# bdm80.net
KiCad netlist of a schematic drawn in EAGLE
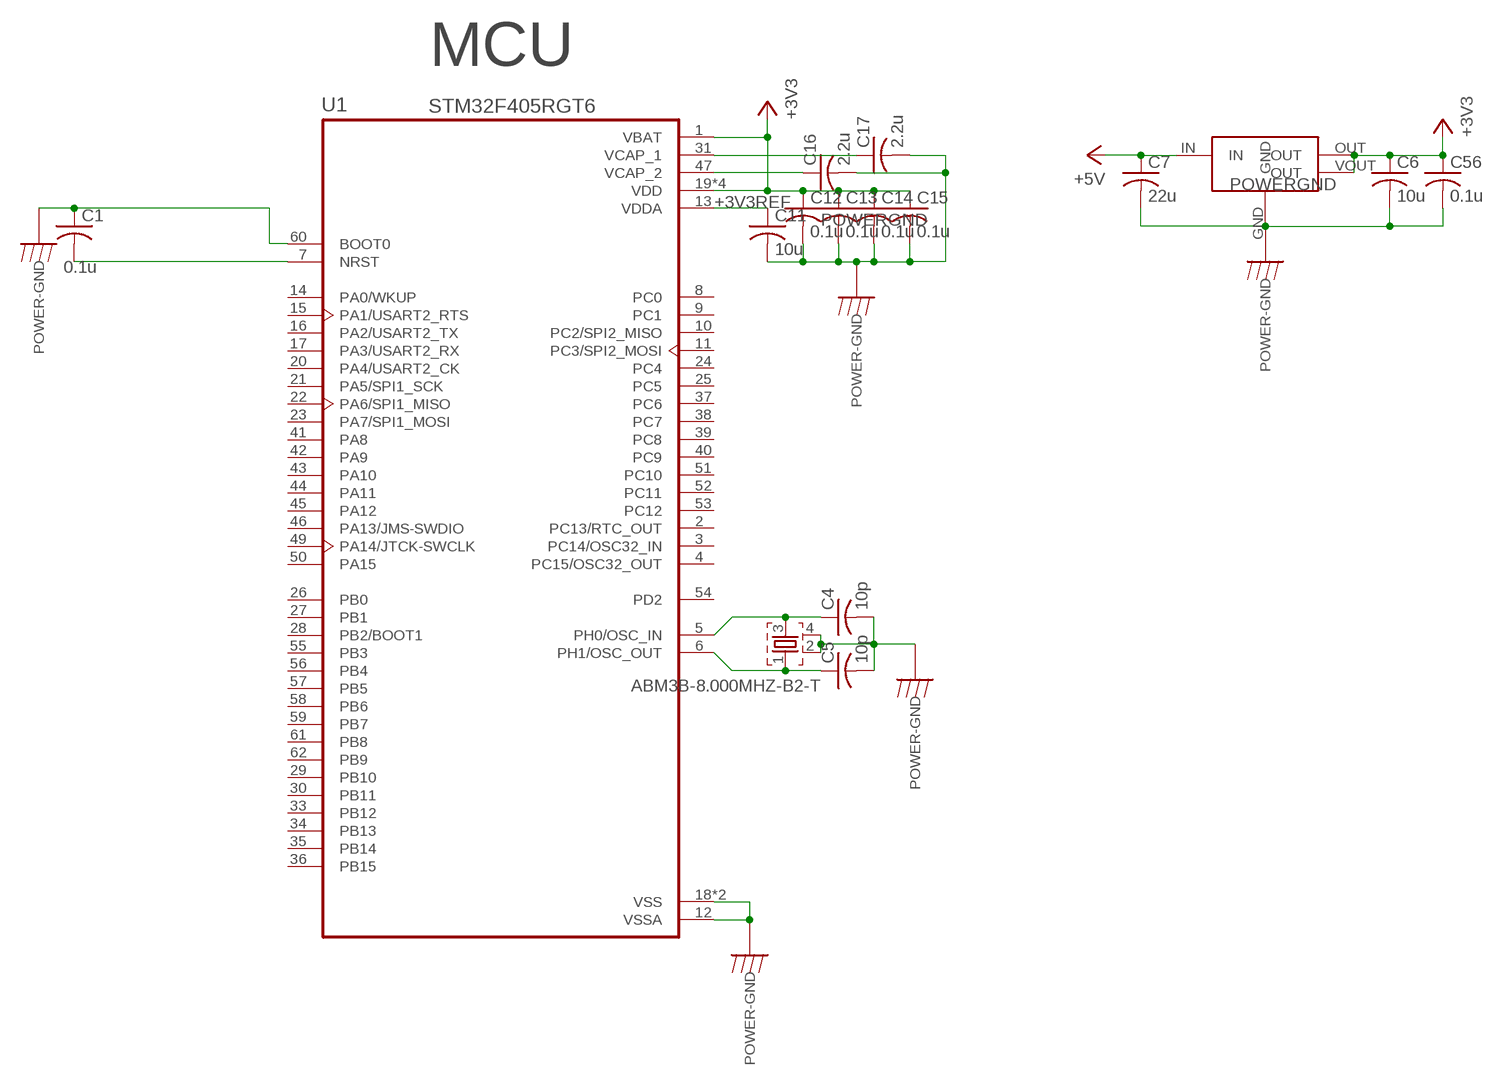
[diagram p0: schematic, sheet 1]

(export (version "E")
  (design (tool "Eeschema 10.0.6"))
  (components
    (comp (ref "C1")
      (value "0.1u")
      (footprint "eagle-import:2012-C")
      (libsource (lib "eagle-import") (part "C-2012"))
    )
    (comp (ref "C4")
      (value "10p")
      (footprint "eagle-import:1608")
      (libsource (lib "eagle-import") (part "C-1608"))
    )
    (comp (ref "C5")
      (value "10p")
      (footprint "eagle-import:1608")
      (libsource (lib "eagle-import") (part "C-1608"))
    )
    (comp (ref "C6")
      (value "10u")
      (footprint "eagle-import:2012-C")
      (libsource (lib "eagle-import") (part "C-2012"))
    )
    (comp (ref "C7")
      (value "22u")
      (footprint "eagle-import:2012-C")
      (libsource (lib "eagle-import") (part "C-2012"))
    )
    (comp (ref "C11")
      (value "10u")
      (footprint "eagle-import:2012-C")
      (libsource (lib "eagle-import") (part "C-2012"))
    )
    (comp (ref "C12")
      (value "0.1u")
      (footprint "eagle-import:2012-C")
      (libsource (lib "eagle-import") (part "C-2012"))
    )
    (comp (ref "C13")
      (value "0.1u")
      (footprint "eagle-import:2012-C")
      (libsource (lib "eagle-import") (part "C-2012"))
    )
    (comp (ref "C14")
      (value "0.1u")
      (footprint "eagle-import:2012-C")
      (libsource (lib "eagle-import") (part "C-2012"))
    )
    (comp (ref "C15")
      (value "0.1u")
      (footprint "eagle-import:2012-C")
      (libsource (lib "eagle-import") (part "C-2012"))
    )
    (comp (ref "C16")
      (value "2.2u")
      (footprint "eagle-import:2012-C")
      (libsource (lib "eagle-import") (part "C-2012"))
    )
    (comp (ref "C17")
      (value "2.2u")
      (footprint "eagle-import:2012-C")
      (libsource (lib "eagle-import") (part "C-2012"))
    )
    (comp (ref "C56")
      (value "0.1u")
      (footprint "eagle-import:2012-C")
      (libsource (lib "eagle-import") (part "C-2012"))
    )
    (comp (ref "IC1")
      (value "AZ1086H-3.3")
      (footprint "eagle-import:SOT223")
      (libsource (lib "eagle-import") (part "AZ1086?-H3.3"))
    )
    (comp (ref "U1")
      (value "STM32F405RGT6")
      (footprint "eagle-import:LQFP64")
      (fields (field (name "DIGI-KEY_PART_NUMBER") "497-11767-ND") (field (name "MF") "STMicroelectronics"))
      (libsource (lib "eagle-import") (part "STM32F405RGT6"))
    )
    (comp (ref "X1")
      (value "ABM3B-8.000MHZ-B2-T")
      (footprint "eagle-import:ABM3B-8.000MHZ-B2-T")
      (libsource (lib "eagle-import") (part "ABM3B-8.000MHZ-B2-T"))
    )
  )
  (nets
    (net (code "1") (name "+3V3") (class "Default")
      (node (ref "C12") (pin "1") (pinfunction "1_1") (pintype "passive"))
      (node (ref "C13") (pin "1") (pinfunction "1_1") (pintype "passive"))
      (node (ref "C14") (pin "1") (pinfunction "1_1") (pintype "passive"))
      (node (ref "C15") (pin "1") (pinfunction "1_1") (pintype "passive"))
      (node (ref "C56") (pin "1") (pinfunction "1_1") (pintype "passive"))
      (node (ref "C6") (pin "1") (pinfunction "1_1") (pintype "passive"))
      (node (ref "IC1") (pin "OUT") (pinfunction "OUT_OUT") (pintype "power_in"))
      (node (ref "IC1") (pin "VOUT") (pinfunction "OUT_VOUT") (pintype "power_in"))
      (node (ref "U1") (pin "1") (pinfunction "VBAT_1") (pintype "power_in"))
      (node (ref "U1") (pin "19") (pinfunction "VDD_19") (pintype "power_in"))
      (node (ref "U1") (pin "32") (pinfunction "VDD_32") (pintype "power_in"))
      (node (ref "U1") (pin "48") (pinfunction "VDD_48") (pintype "power_in"))
      (node (ref "U1") (pin "64") (pinfunction "VDD_64") (pintype "power_in"))
    )
    (net (code "2") (name "+5V") (class "Default")
      (node (ref "C7") (pin "1") (pinfunction "1_1") (pintype "passive"))
      (node (ref "IC1") (pin "IN") (pinfunction "IN_IN") (pintype "power_in"))
    )
    (net (code "3") (name "/+3V3REF") (class "Default")
      (node (ref "C11") (pin "1") (pinfunction "1_1") (pintype "passive"))
      (node (ref "U1") (pin "13") (pinfunction "VDDA_13") (pintype "power_in"))
    )
    (net (code "4") (name "Net-(U1-NRST)") (class "Default")
      (node (ref "C1") (pin "2") (pinfunction "2_2") (pintype "passive"))
      (node (ref "U1") (pin "7") (pinfunction "NRST_7") (pintype "bidirectional"))
    )
    (net (code "5") (name "Net-(U1-PH0{slash}OSC_IN)") (class "Default")
      (node (ref "C4") (pin "1") (pinfunction "1_1") (pintype "passive"))
      (node (ref "U1") (pin "5") (pinfunction "PH0/OSC_IN_5") (pintype "bidirectional"))
      (node (ref "X1") (pin "3") (pinfunction "3_3") (pintype "passive"))
    )
    (net (code "6") (name "Net-(U1-PH1{slash}OSC_OUT)") (class "Default")
      (node (ref "C5") (pin "1") (pinfunction "1_1") (pintype "passive"))
      (node (ref "U1") (pin "6") (pinfunction "PH1/OSC_OUT_6") (pintype "bidirectional"))
      (node (ref "X1") (pin "1") (pinfunction "1_1") (pintype "passive"))
    )
    (net (code "7") (name "Net-(U1-VCAP_1)") (class "Default")
      (node (ref "C17") (pin "1") (pinfunction "1_1") (pintype "passive"))
      (node (ref "U1") (pin "31") (pinfunction "VCAP_1_31") (pintype "power_in"))
    )
    (net (code "8") (name "Net-(U1-VCAP_2)") (class "Default")
      (node (ref "C16") (pin "1") (pinfunction "1_1") (pintype "passive"))
      (node (ref "U1") (pin "47") (pinfunction "VCAP_2_47") (pintype "power_in"))
    )
    (net (code "9") (name "POWERGND") (class "Default")
      (node (ref "C1") (pin "1") (pinfunction "1_1") (pintype "passive"))
      (node (ref "C11") (pin "2") (pinfunction "2_2") (pintype "passive"))
      (node (ref "C12") (pin "2") (pinfunction "2_2") (pintype "passive"))
      (node (ref "C13") (pin "2") (pinfunction "2_2") (pintype "passive"))
      (node (ref "C14") (pin "2") (pinfunction "2_2") (pintype "passive"))
      (node (ref "C15") (pin "2") (pinfunction "2_2") (pintype "passive"))
      (node (ref "C16") (pin "2") (pinfunction "2_2") (pintype "passive"))
      (node (ref "C17") (pin "2") (pinfunction "2_2") (pintype "passive"))
      (node (ref "C4") (pin "2") (pinfunction "2_2") (pintype "passive"))
      (node (ref "C5") (pin "2") (pinfunction "2_2") (pintype "passive"))
      (node (ref "C56") (pin "2") (pinfunction "2_2") (pintype "passive"))
      (node (ref "C6") (pin "2") (pinfunction "2_2") (pintype "passive"))
      (node (ref "C7") (pin "2") (pinfunction "2_2") (pintype "passive"))
      (node (ref "IC1") (pin "GND") (pinfunction "GND_GND") (pintype "power_in"))
      (node (ref "U1") (pin "12") (pinfunction "VSSA_12") (pintype "power_in"))
      (node (ref "U1") (pin "18") (pinfunction "VSS_18") (pintype "power_in"))
      (node (ref "U1") (pin "60") (pinfunction "BOOT0_60") (pintype "bidirectional"))
      (node (ref "U1") (pin "63") (pinfunction "VSS_63") (pintype "power_in"))
      (node (ref "X1") (pin "2") (pinfunction "2_2") (pintype "passive"))
      (node (ref "X1") (pin "4") (pinfunction "4_4") (pintype "passive"))
    )
    (net (code "10") (name "unconnected-(U1-PA0{slash}WKUP-Pad14)") (class "Default")
      (node (ref "U1") (pin "14") (pinfunction "PA0/WKUP_14") (pintype "bidirectional"))
    )
    (net (code "11") (name "unconnected-(U1-PA1{slash}USART2_RTS-Pad15)") (class "Default")
      (node (ref "U1") (pin "15") (pinfunction "PA1/USART2_RTS_15") (pintype "bidirectional"))
    )
    (net (code "12") (name "unconnected-(U1-PA2{slash}USART2_TX-Pad16)") (class "Default")
      (node (ref "U1") (pin "16") (pinfunction "PA2/USART2_TX_16") (pintype "bidirectional"))
    )
    (net (code "13") (name "unconnected-(U1-PA3{slash}USART2_RX-Pad17)") (class "Default")
      (node (ref "U1") (pin "17") (pinfunction "PA3/USART2_RX_17") (pintype "bidirectional"))
    )
    (net (code "14") (name "unconnected-(U1-PA4{slash}USART2_CK-Pad20)") (class "Default")
      (node (ref "U1") (pin "20") (pinfunction "PA4/USART2_CK_20") (pintype "bidirectional"))
    )
    (net (code "15") (name "unconnected-(U1-PA5{slash}SPI1_SCK-Pad21)") (class "Default")
      (node (ref "U1") (pin "21") (pinfunction "PA5/SPI1_SCK_21") (pintype "bidirectional"))
    )
    (net (code "16") (name "unconnected-(U1-PA6{slash}SPI1_MISO-Pad22)") (class "Default")
      (node (ref "U1") (pin "22") (pinfunction "PA6/SPI1_MISO_22") (pintype "bidirectional"))
    )
    (net (code "17") (name "unconnected-(U1-PA7{slash}SPI1_MOSI-Pad23)") (class "Default")
      (node (ref "U1") (pin "23") (pinfunction "PA7/SPI1_MOSI_23") (pintype "bidirectional"))
    )
    (net (code "18") (name "unconnected-(U1-PA8-Pad41)") (class "Default")
      (node (ref "U1") (pin "41") (pinfunction "PA8_41") (pintype "bidirectional"))
    )
    (net (code "19") (name "unconnected-(U1-PA9-Pad42)") (class "Default")
      (node (ref "U1") (pin "42") (pinfunction "PA9_42") (pintype "bidirectional"))
    )
    (net (code "20") (name "unconnected-(U1-PA10-Pad43)") (class "Default")
      (node (ref "U1") (pin "43") (pinfunction "PA10_43") (pintype "bidirectional"))
    )
    (net (code "21") (name "unconnected-(U1-PA11-Pad44)") (class "Default")
      (node (ref "U1") (pin "44") (pinfunction "PA11_44") (pintype "bidirectional"))
    )
    (net (code "22") (name "unconnected-(U1-PA12-Pad45)") (class "Default")
      (node (ref "U1") (pin "45") (pinfunction "PA12_45") (pintype "bidirectional"))
    )
    (net (code "23") (name "unconnected-(U1-PA13{slash}JMS-SWDIO-Pad46)") (class "Default")
      (node (ref "U1") (pin "46") (pinfunction "PA13/JMS-SWDIO_46") (pintype "bidirectional"))
    )
    (net (code "24") (name "unconnected-(U1-PA14{slash}JTCK-SWCLK-Pad49)") (class "Default")
      (node (ref "U1") (pin "49") (pinfunction "PA14/JTCK-SWCLK_49") (pintype "bidirectional"))
    )
    (net (code "25") (name "unconnected-(U1-PA15-Pad50)") (class "Default")
      (node (ref "U1") (pin "50") (pinfunction "PA15_50") (pintype "bidirectional"))
    )
    (net (code "26") (name "unconnected-(U1-PB0-Pad26)") (class "Default")
      (node (ref "U1") (pin "26") (pinfunction "PB0_26") (pintype "bidirectional"))
    )
    (net (code "27") (name "unconnected-(U1-PB1-Pad27)") (class "Default")
      (node (ref "U1") (pin "27") (pinfunction "PB1_27") (pintype "bidirectional"))
    )
    (net (code "28") (name "unconnected-(U1-PB2{slash}BOOT1-Pad28)") (class "Default")
      (node (ref "U1") (pin "28") (pinfunction "PB2/BOOT1_28") (pintype "bidirectional"))
    )
    (net (code "29") (name "unconnected-(U1-PB3-Pad55)") (class "Default")
      (node (ref "U1") (pin "55") (pinfunction "PB3_55") (pintype "bidirectional"))
    )
    (net (code "30") (name "unconnected-(U1-PB4-Pad56)") (class "Default")
      (node (ref "U1") (pin "56") (pinfunction "PB4_56") (pintype "bidirectional"))
    )
    (net (code "31") (name "unconnected-(U1-PB5-Pad57)") (class "Default")
      (node (ref "U1") (pin "57") (pinfunction "PB5_57") (pintype "bidirectional"))
    )
    (net (code "32") (name "unconnected-(U1-PB6-Pad58)") (class "Default")
      (node (ref "U1") (pin "58") (pinfunction "PB6_58") (pintype "bidirectional"))
    )
    (net (code "33") (name "unconnected-(U1-PB7-Pad59)") (class "Default")
      (node (ref "U1") (pin "59") (pinfunction "PB7_59") (pintype "bidirectional"))
    )
    (net (code "34") (name "unconnected-(U1-PB8-Pad61)") (class "Default")
      (node (ref "U1") (pin "61") (pinfunction "PB8_61") (pintype "bidirectional"))
    )
    (net (code "35") (name "unconnected-(U1-PB9-Pad62)") (class "Default")
      (node (ref "U1") (pin "62") (pinfunction "PB9_62") (pintype "bidirectional"))
    )
    (net (code "36") (name "unconnected-(U1-PB10-Pad29)") (class "Default")
      (node (ref "U1") (pin "29") (pinfunction "PB10_29") (pintype "bidirectional"))
    )
    (net (code "37") (name "unconnected-(U1-PB11-Pad30)") (class "Default")
      (node (ref "U1") (pin "30") (pinfunction "PB11_30") (pintype "bidirectional"))
    )
    (net (code "38") (name "unconnected-(U1-PB12-Pad33)") (class "Default")
      (node (ref "U1") (pin "33") (pinfunction "PB12_33") (pintype "bidirectional"))
    )
    (net (code "39") (name "unconnected-(U1-PB13-Pad34)") (class "Default")
      (node (ref "U1") (pin "34") (pinfunction "PB13_34") (pintype "bidirectional"))
    )
    (net (code "40") (name "unconnected-(U1-PB14-Pad35)") (class "Default")
      (node (ref "U1") (pin "35") (pinfunction "PB14_35") (pintype "bidirectional"))
    )
    (net (code "41") (name "unconnected-(U1-PB15-Pad36)") (class "Default")
      (node (ref "U1") (pin "36") (pinfunction "PB15_36") (pintype "bidirectional"))
    )
    (net (code "42") (name "unconnected-(U1-PC0-Pad8)") (class "Default")
      (node (ref "U1") (pin "8") (pinfunction "PC0_8") (pintype "bidirectional"))
    )
    (net (code "43") (name "unconnected-(U1-PC1-Pad9)") (class "Default")
      (node (ref "U1") (pin "9") (pinfunction "PC1_9") (pintype "bidirectional"))
    )
    (net (code "44") (name "unconnected-(U1-PC2{slash}SPI2_MISO-Pad10)") (class "Default")
      (node (ref "U1") (pin "10") (pinfunction "PC2/SPI2_MISO_10") (pintype "bidirectional"))
    )
    (net (code "45") (name "unconnected-(U1-PC3{slash}SPI2_MOSI-Pad11)") (class "Default")
      (node (ref "U1") (pin "11") (pinfunction "PC3/SPI2_MOSI_11") (pintype "bidirectional"))
    )
    (net (code "46") (name "unconnected-(U1-PC4-Pad24)") (class "Default")
      (node (ref "U1") (pin "24") (pinfunction "PC4_24") (pintype "bidirectional"))
    )
    (net (code "47") (name "unconnected-(U1-PC5-Pad25)") (class "Default")
      (node (ref "U1") (pin "25") (pinfunction "PC5_25") (pintype "bidirectional"))
    )
    (net (code "48") (name "unconnected-(U1-PC6-Pad37)") (class "Default")
      (node (ref "U1") (pin "37") (pinfunction "PC6_37") (pintype "bidirectional"))
    )
    (net (code "49") (name "unconnected-(U1-PC7-Pad38)") (class "Default")
      (node (ref "U1") (pin "38") (pinfunction "PC7_38") (pintype "bidirectional"))
    )
    (net (code "50") (name "unconnected-(U1-PC8-Pad39)") (class "Default")
      (node (ref "U1") (pin "39") (pinfunction "PC8_39") (pintype "bidirectional"))
    )
    (net (code "51") (name "unconnected-(U1-PC9-Pad40)") (class "Default")
      (node (ref "U1") (pin "40") (pinfunction "PC9_40") (pintype "bidirectional"))
    )
    (net (code "52") (name "unconnected-(U1-PC10-Pad51)") (class "Default")
      (node (ref "U1") (pin "51") (pinfunction "PC10_51") (pintype "bidirectional"))
    )
    (net (code "53") (name "unconnected-(U1-PC11-Pad52)") (class "Default")
      (node (ref "U1") (pin "52") (pinfunction "PC11_52") (pintype "bidirectional"))
    )
    (net (code "54") (name "unconnected-(U1-PC12-Pad53)") (class "Default")
      (node (ref "U1") (pin "53") (pinfunction "PC12_53") (pintype "bidirectional"))
    )
    (net (code "55") (name "unconnected-(U1-PC13{slash}RTC_OUT-Pad2)") (class "Default")
      (node (ref "U1") (pin "2") (pinfunction "PC13/RTC_OUT_2") (pintype "bidirectional"))
    )
    (net (code "56") (name "unconnected-(U1-PC14{slash}OSC32_IN-Pad3)") (class "Default")
      (node (ref "U1") (pin "3") (pinfunction "PC14/OSC32_IN_3") (pintype "bidirectional"))
    )
    (net (code "57") (name "unconnected-(U1-PC15{slash}OSC32_OUT-Pad4)") (class "Default")
      (node (ref "U1") (pin "4") (pinfunction "PC15/OSC32_OUT_4") (pintype "bidirectional"))
    )
    (net (code "58") (name "unconnected-(U1-PD2-Pad54)") (class "Default")
      (node (ref "U1") (pin "54") (pinfunction "PD2_54") (pintype "bidirectional"))
    )
  )
)
